# VCA-3080_MB.net
KiCad netlist of a schematic drawn in EAGLE
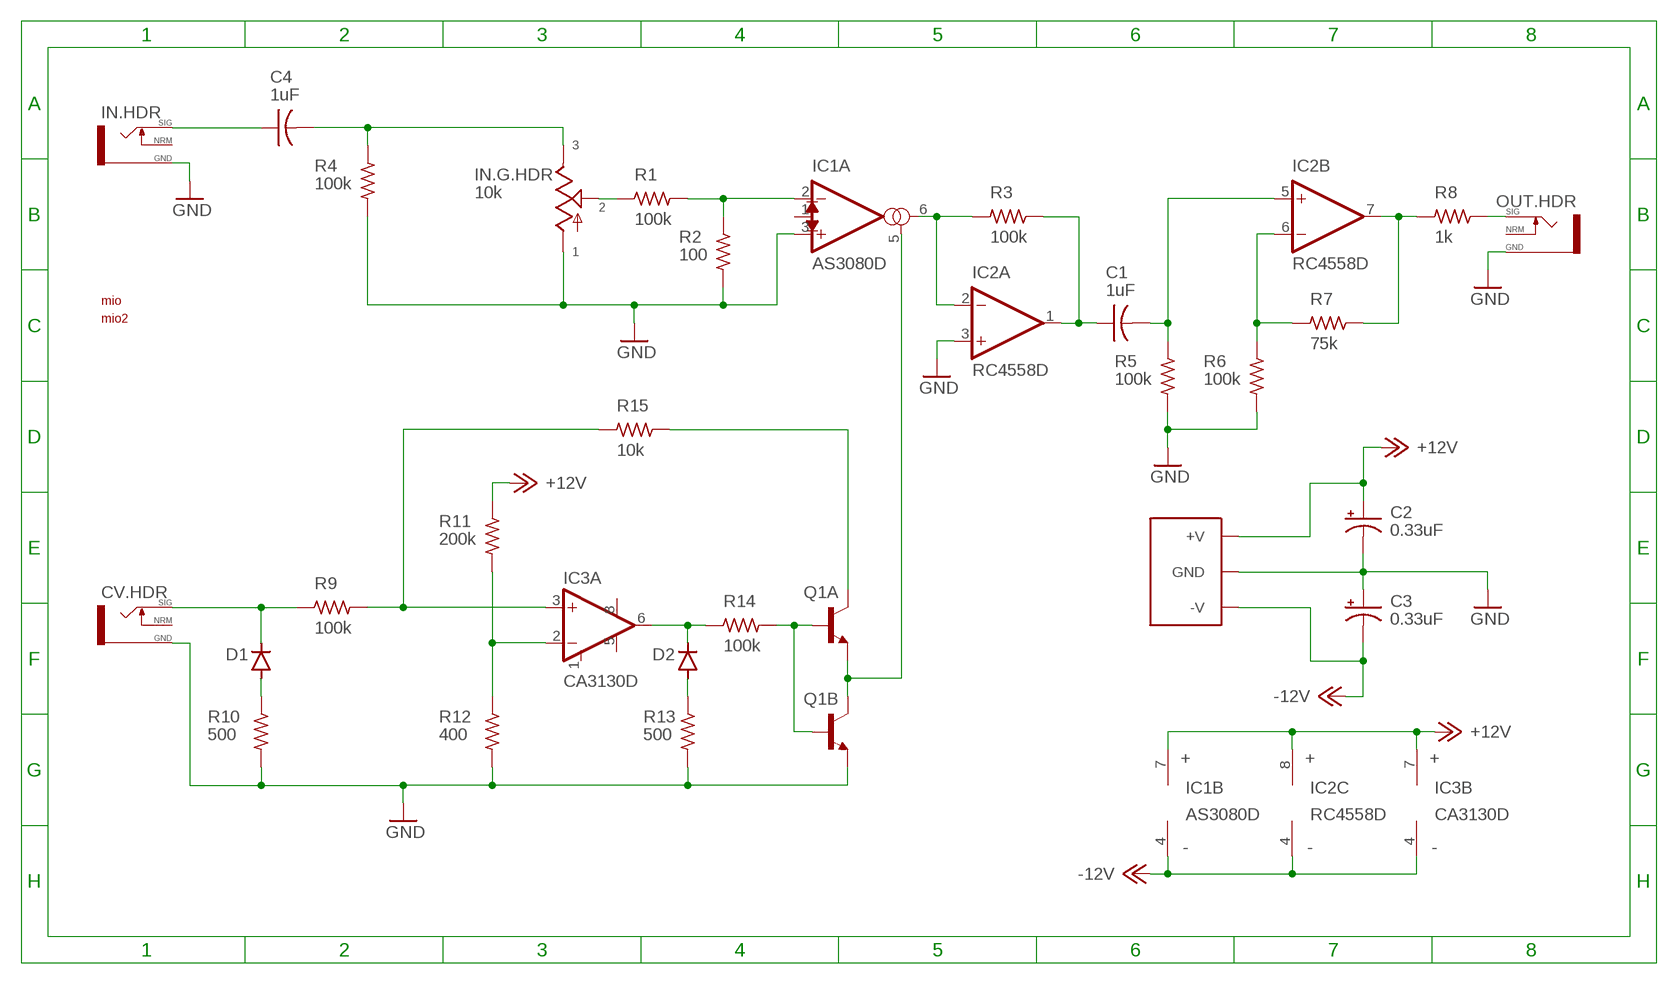
[diagram p0: schematic, sheet 1]

(export (version "E")
  (design (tool "Eeschema 10.0.6"))
  (components
    (comp (ref "C1")
      (value "1uF")
      (footprint "eagle-import:C05")
      (libsource (lib "eagle-import") (part "C-05"))
    )
    (comp (ref "C2")
      (value "0.33uF")
      (footprint "eagle-import:E025")
      (libsource (lib "eagle-import") (part "CPOL-E025"))
    )
    (comp (ref "C3")
      (value "0.33uF")
      (footprint "eagle-import:E025")
      (libsource (lib "eagle-import") (part "CPOL-E025"))
    )
    (comp (ref "C4")
      (value "1uF")
      (footprint "eagle-import:C05")
      (libsource (lib "eagle-import") (part "C-05"))
    )
    (comp (ref "CV.HDR")
      (value "MONOHDR")
      (footprint "eagle-import:HEADER")
      (libsource (lib "eagle-import") (part "MONOHDR"))
    )
    (comp (ref "D1")
      (value "D-123")
      (footprint "eagle-import:SOD-123")
      (libsource (lib "eagle-import") (part "D-123"))
    )
    (comp (ref "D2")
      (value "D-123")
      (footprint "eagle-import:SOD-123")
      (libsource (lib "eagle-import") (part "D-123"))
    )
    (comp (ref "IC1")
      (value "AS3080D")
      (footprint "eagle-import:DIL08")
      (libsource (lib "eagle-import") (part "AS3080D"))
    )
    (comp (ref "IC2")
      (value "RC4558D")
      (footprint "eagle-import:DIL08")
      (libsource (lib "eagle-import") (part "RC4558D"))
    )
    (comp (ref "IC3")
      (value "CA3130D")
      (footprint "eagle-import:DIL08")
      (libsource (lib "eagle-import") (part "CA3130D"))
    )
    (comp (ref "IN.G.HDR")
      (value "10k")
      (footprint "eagle-import:HEADER")
      (libsource (lib "eagle-import") (part "PHDR"))
    )
    (comp (ref "IN.HDR")
      (value "MONOHDR")
      (footprint "eagle-import:HEADER")
      (libsource (lib "eagle-import") (part "MONOHDR"))
    )
    (comp (ref "OUT.HDR")
      (value "MONOHDR")
      (footprint "eagle-import:HEADER")
      (libsource (lib "eagle-import") (part "MONOHDR"))
    )
    (comp (ref "Q1")
      (value "BCM847DS")
      (footprint "eagle-import:SOT-23-6")
      (libsource (lib "eagle-import") (part "BCM847DS"))
    )
    (comp (ref "R1")
      (value "100k")
      (footprint "eagle-import:R1206")
      (libsource (lib "eagle-import") (part "R-1206"))
    )
    (comp (ref "R2")
      (value "100")
      (footprint "eagle-import:R1206")
      (libsource (lib "eagle-import") (part "R-1206"))
    )
    (comp (ref "R3")
      (value "100k")
      (footprint "eagle-import:R1206")
      (libsource (lib "eagle-import") (part "R-1206"))
    )
    (comp (ref "R4")
      (value "100k")
      (footprint "eagle-import:R1206")
      (libsource (lib "eagle-import") (part "R-1206"))
    )
    (comp (ref "R5")
      (value "100k")
      (footprint "eagle-import:R1206")
      (libsource (lib "eagle-import") (part "R-1206"))
    )
    (comp (ref "R6")
      (value "100k")
      (footprint "eagle-import:R1206")
      (libsource (lib "eagle-import") (part "R-1206"))
    )
    (comp (ref "R7")
      (value "75k")
      (footprint "eagle-import:R1206")
      (libsource (lib "eagle-import") (part "R-1206"))
    )
    (comp (ref "R8")
      (value "1k")
      (footprint "eagle-import:R1206")
      (libsource (lib "eagle-import") (part "R-1206"))
    )
    (comp (ref "R9")
      (value "100k")
      (footprint "eagle-import:R1206")
      (libsource (lib "eagle-import") (part "R-1206"))
    )
    (comp (ref "R10")
      (value "500")
      (footprint "eagle-import:R1206")
      (libsource (lib "eagle-import") (part "R-1206"))
    )
    (comp (ref "R11")
      (value "200k")
      (footprint "eagle-import:R1206")
      (libsource (lib "eagle-import") (part "R-1206"))
    )
    (comp (ref "R12")
      (value "400")
      (footprint "eagle-import:R1206")
      (libsource (lib "eagle-import") (part "R-1206"))
    )
    (comp (ref "R13")
      (value "500")
      (footprint "eagle-import:R1206")
      (libsource (lib "eagle-import") (part "R-1206"))
    )
    (comp (ref "R14")
      (value "100k")
      (footprint "eagle-import:R1206")
      (libsource (lib "eagle-import") (part "R-1206"))
    )
    (comp (ref "R15")
      (value "10k")
      (footprint "eagle-import:R1206")
      (libsource (lib "eagle-import") (part "R-1206"))
    )
    (comp (ref "U$1")
      (value "10PIN-PWR")
      (footprint "eagle-import:10PIN-HEADER")
      (libsource (lib "eagle-import") (part "10PIN-PWR"))
    )
    (comp (ref "U$2")
      (value "MIO")
      (footprint "eagle-import:MIO")
      (libsource (lib "eagle-import") (part "MIO"))
    )
    (comp (ref "U$3")
      (value "MIO2")
      (footprint "eagle-import:MIO2")
      (libsource (lib "eagle-import") (part "MIO2"))
    )
  )
  (nets
    (net (code "1") (name "+12V") (class "Default")
      (node (ref "C2") (pin "+") (pinfunction "+_+") (pintype "passive"))
      (node (ref "IC1") (pin "7") (pinfunction "V+_7") (pintype "power_in"))
      (node (ref "IC2") (pin "8") (pinfunction "V+_8") (pintype "power_in"))
      (node (ref "IC3") (pin "7") (pinfunction "V+_7") (pintype "power_in"))
      (node (ref "R11") (pin "2") (pinfunction "2_2") (pintype "passive"))
      (node (ref "U$1") (pin "10") (pinfunction "+V_10") (pintype "bidirectional"))
      (node (ref "U$1") (pin "9") (pinfunction "+V_9") (pintype "bidirectional"))
    )
    (net (code "2") (name "-12V") (class "Default")
      (node (ref "C3") (pin "-") (pinfunction "-_-") (pintype "passive"))
      (node (ref "IC1") (pin "4") (pinfunction "V-_4") (pintype "power_in"))
      (node (ref "IC2") (pin "4") (pinfunction "V-_4") (pintype "power_in"))
      (node (ref "IC3") (pin "4") (pinfunction "V-_4") (pintype "power_in"))
      (node (ref "U$1") (pin "1") (pinfunction "-V_1") (pintype "bidirectional"))
      (node (ref "U$1") (pin "2") (pinfunction "-V_2") (pintype "bidirectional"))
    )
    (net (code "3") (name "GND") (class "Default")
      (node (ref "C2") (pin "-") (pinfunction "-_-") (pintype "passive"))
      (node (ref "C3") (pin "+") (pinfunction "+_+") (pintype "passive"))
      (node (ref "CV.HDR") (pin "GND") (pinfunction "SLEEVE-GND_GND") (pintype "passive"))
      (node (ref "IC1") (pin "3") (pinfunction "NON-INVERTING(+)_3") (pintype "input"))
      (node (ref "IC2") (pin "3") (pinfunction "NON-INVERTING(+)_3") (pintype "input"))
      (node (ref "IN.G.HDR") (pin "1") (pinfunction "1_1") (pintype "passive"))
      (node (ref "IN.HDR") (pin "GND") (pinfunction "SLEEVE-GND_GND") (pintype "passive"))
      (node (ref "OUT.HDR") (pin "GND") (pinfunction "SLEEVE-GND_GND") (pintype "passive"))
      (node (ref "Q1") (pin "4") (pinfunction "E_4") (pintype "bidirectional"))
      (node (ref "R10") (pin "1") (pinfunction "1_1") (pintype "passive"))
      (node (ref "R12") (pin "1") (pinfunction "1_1") (pintype "passive"))
      (node (ref "R13") (pin "1") (pinfunction "1_1") (pintype "passive"))
      (node (ref "R2") (pin "1") (pinfunction "1_1") (pintype "passive"))
      (node (ref "R4") (pin "1") (pinfunction "1_1") (pintype "passive"))
      (node (ref "R5") (pin "1") (pinfunction "1_1") (pintype "passive"))
      (node (ref "R6") (pin "1") (pinfunction "1_1") (pintype "passive"))
      (node (ref "U$1") (pin "3") (pinfunction "GND_3") (pintype "bidirectional"))
      (node (ref "U$1") (pin "4") (pinfunction "GND_4") (pintype "bidirectional"))
      (node (ref "U$1") (pin "5") (pinfunction "GND_5") (pintype "bidirectional"))
      (node (ref "U$1") (pin "6") (pinfunction "GND_6") (pintype "bidirectional"))
      (node (ref "U$1") (pin "7") (pinfunction "GND_7") (pintype "bidirectional"))
      (node (ref "U$1") (pin "8") (pinfunction "GND_8") (pintype "bidirectional"))
    )
    (net (code "4") (name "Net-(C4-Pad1)") (class "Default")
      (node (ref "C4") (pin "1") (pinfunction "1_1") (pintype "passive"))
      (node (ref "IN.HDR") (pin "TIP-SIG") (pinfunction "TIP-SIG_TIP-SIG") (pintype "passive"))
    )
    (net (code "5") (name "Net-(C4-Pad2)") (class "Default")
      (node (ref "C4") (pin "2") (pinfunction "2_2") (pintype "passive"))
      (node (ref "IN.G.HDR") (pin "3") (pinfunction "3_3") (pintype "passive"))
      (node (ref "R4") (pin "2") (pinfunction "2_2") (pintype "passive"))
    )
    (net (code "6") (name "Net-(CV.HDR-PadTIP-SIG)") (class "Default")
      (node (ref "CV.HDR") (pin "TIP-SIG") (pinfunction "TIP-SIG_TIP-SIG") (pintype "passive"))
      (node (ref "D1") (pin "C") (pinfunction "C_C") (pintype "passive"))
      (node (ref "R9") (pin "1") (pinfunction "1_1") (pintype "passive"))
    )
    (net (code "7") (name "Net-(D1-PadA)") (class "Default")
      (node (ref "D1") (pin "A") (pinfunction "A_A") (pintype "passive"))
      (node (ref "R10") (pin "2") (pinfunction "2_2") (pintype "passive"))
    )
    (net (code "8") (name "Net-(D2-PadA)") (class "Default")
      (node (ref "D2") (pin "A") (pinfunction "A_A") (pintype "passive"))
      (node (ref "R13") (pin "2") (pinfunction "2_2") (pintype "passive"))
    )
    (net (code "9") (name "Net-(IC1A-I-BIAS)") (class "Default")
      (node (ref "IC1") (pin "5") (pinfunction "I-BIAS_5") (pintype "input"))
      (node (ref "Q1") (pin "1") (pinfunction "E_1") (pintype "bidirectional"))
      (node (ref "Q1") (pin "3") (pinfunction "C_3") (pintype "bidirectional"))
    )
    (net (code "10") (name "Net-(IC1A-INVERTING(-))") (class "Default")
      (node (ref "IC1") (pin "2") (pinfunction "INVERTING(-)_2") (pintype "input"))
      (node (ref "R1") (pin "2") (pinfunction "2_2") (pintype "passive"))
      (node (ref "R2") (pin "2") (pinfunction "2_2") (pintype "passive"))
    )
    (net (code "11") (name "Net-(IC1A-OUT)") (class "Default")
      (node (ref "IC1") (pin "6") (pinfunction "OUT_6") (pintype "output"))
      (node (ref "IC2") (pin "2") (pinfunction "INVERTING(-)_2") (pintype "input"))
      (node (ref "R3") (pin "1") (pinfunction "1_1") (pintype "passive"))
    )
    (net (code "12") (name "Net-(IC2A-OUT)") (class "Default")
      (node (ref "C1") (pin "1") (pinfunction "1_1") (pintype "passive"))
      (node (ref "IC2") (pin "1") (pinfunction "OUT_1") (pintype "output"))
      (node (ref "R3") (pin "2") (pinfunction "2_2") (pintype "passive"))
    )
    (net (code "13") (name "Net-(IC2B-INVERTING(-))") (class "Default")
      (node (ref "IC2") (pin "6") (pinfunction "INVERTING(-)_6") (pintype "input"))
      (node (ref "R6") (pin "2") (pinfunction "2_2") (pintype "passive"))
      (node (ref "R7") (pin "1") (pinfunction "1_1") (pintype "passive"))
    )
    (net (code "14") (name "Net-(IC2B-NON-INVERTING(+))") (class "Default")
      (node (ref "C1") (pin "2") (pinfunction "2_2") (pintype "passive"))
      (node (ref "IC2") (pin "5") (pinfunction "NON-INVERTING(+)_5") (pintype "input"))
      (node (ref "R5") (pin "2") (pinfunction "2_2") (pintype "passive"))
    )
    (net (code "15") (name "Net-(IC2B-OUT)") (class "Default")
      (node (ref "IC2") (pin "7") (pinfunction "OUT_7") (pintype "output"))
      (node (ref "R7") (pin "2") (pinfunction "2_2") (pintype "passive"))
      (node (ref "R8") (pin "1") (pinfunction "1_1") (pintype "passive"))
    )
    (net (code "16") (name "Net-(IC3A-INVERTINGA(-))") (class "Default")
      (node (ref "IC3") (pin "2") (pinfunction "INVERTINGA(-)_2") (pintype "input"))
      (node (ref "R11") (pin "1") (pinfunction "1_1") (pintype "passive"))
      (node (ref "R12") (pin "2") (pinfunction "2_2") (pintype "passive"))
    )
    (net (code "17") (name "Net-(IC3A-NON-INVERTING(+))") (class "Default")
      (node (ref "IC3") (pin "3") (pinfunction "NON-INVERTING(+)_3") (pintype "input"))
      (node (ref "R15") (pin "1") (pinfunction "1_1") (pintype "passive"))
      (node (ref "R9") (pin "2") (pinfunction "2_2") (pintype "passive"))
    )
    (net (code "18") (name "Net-(IC3A-OUT)") (class "Default")
      (node (ref "D2") (pin "C") (pinfunction "C_C") (pintype "passive"))
      (node (ref "IC3") (pin "6") (pinfunction "OUT_6") (pintype "output"))
      (node (ref "R14") (pin "1") (pinfunction "1_1") (pintype "passive"))
    )
    (net (code "19") (name "Net-(IN.G.HDR-Pad2)") (class "Default")
      (node (ref "IN.G.HDR") (pin "2") (pinfunction "2_2") (pintype "passive"))
      (node (ref "R1") (pin "1") (pinfunction "1_1") (pintype "passive"))
    )
    (net (code "20") (name "Net-(OUT.HDR-PadTIP-SIG)") (class "Default")
      (node (ref "OUT.HDR") (pin "TIP-SIG") (pinfunction "TIP-SIG_TIP-SIG") (pintype "passive"))
      (node (ref "R8") (pin "2") (pinfunction "2_2") (pintype "passive"))
    )
    (net (code "21") (name "Net-(Q1A-B)") (class "Default")
      (node (ref "Q1") (pin "2") (pinfunction "B_2") (pintype "bidirectional"))
      (node (ref "Q1") (pin "5") (pinfunction "B_5") (pintype "bidirectional"))
      (node (ref "R14") (pin "2") (pinfunction "2_2") (pintype "passive"))
    )
    (net (code "22") (name "Net-(Q1A-C)") (class "Default")
      (node (ref "Q1") (pin "6") (pinfunction "C_6") (pintype "bidirectional"))
      (node (ref "R15") (pin "2") (pinfunction "2_2") (pintype "passive"))
    )
    (net (code "23") (name "unconnected-(CV.HDR-SWITCH-NORM-PadNORM)") (class "Default")
      (node (ref "CV.HDR") (pin "NORM") (pinfunction "SWITCH-NORM_NORM") (pintype "passive"))
    )
    (net (code "24") (name "unconnected-(IC1A-D-BIAS-Pad1)") (class "Default")
      (node (ref "IC1") (pin "1") (pinfunction "D-BIAS_1") (pintype "input"))
    )
    (net (code "25") (name "unconnected-(IC3A-NULL(1)-Pad1)") (class "Default")
      (node (ref "IC3") (pin "1") (pinfunction "NULL(1)_1") (pintype "input"))
    )
    (net (code "26") (name "unconnected-(IC3A-NULL(5)-Pad5)") (class "Default")
      (node (ref "IC3") (pin "5") (pinfunction "NULL(5)_5") (pintype "input"))
    )
    (net (code "27") (name "unconnected-(IC3A-STRB-Pad8)") (class "Default")
      (node (ref "IC3") (pin "8") (pinfunction "STRB_8") (pintype "input"))
    )
    (net (code "28") (name "unconnected-(IN.HDR-SWITCH-NORM-PadNORM)") (class "Default")
      (node (ref "IN.HDR") (pin "NORM") (pinfunction "SWITCH-NORM_NORM") (pintype "passive"))
    )
    (net (code "29") (name "unconnected-(OUT.HDR-SWITCH-NORM-PadNORM)") (class "Default")
      (node (ref "OUT.HDR") (pin "NORM") (pinfunction "SWITCH-NORM_NORM") (pintype "passive"))
    )
  )
)
